# BedStrip.net
KiCad netlist of a schematic drawn in EAGLE
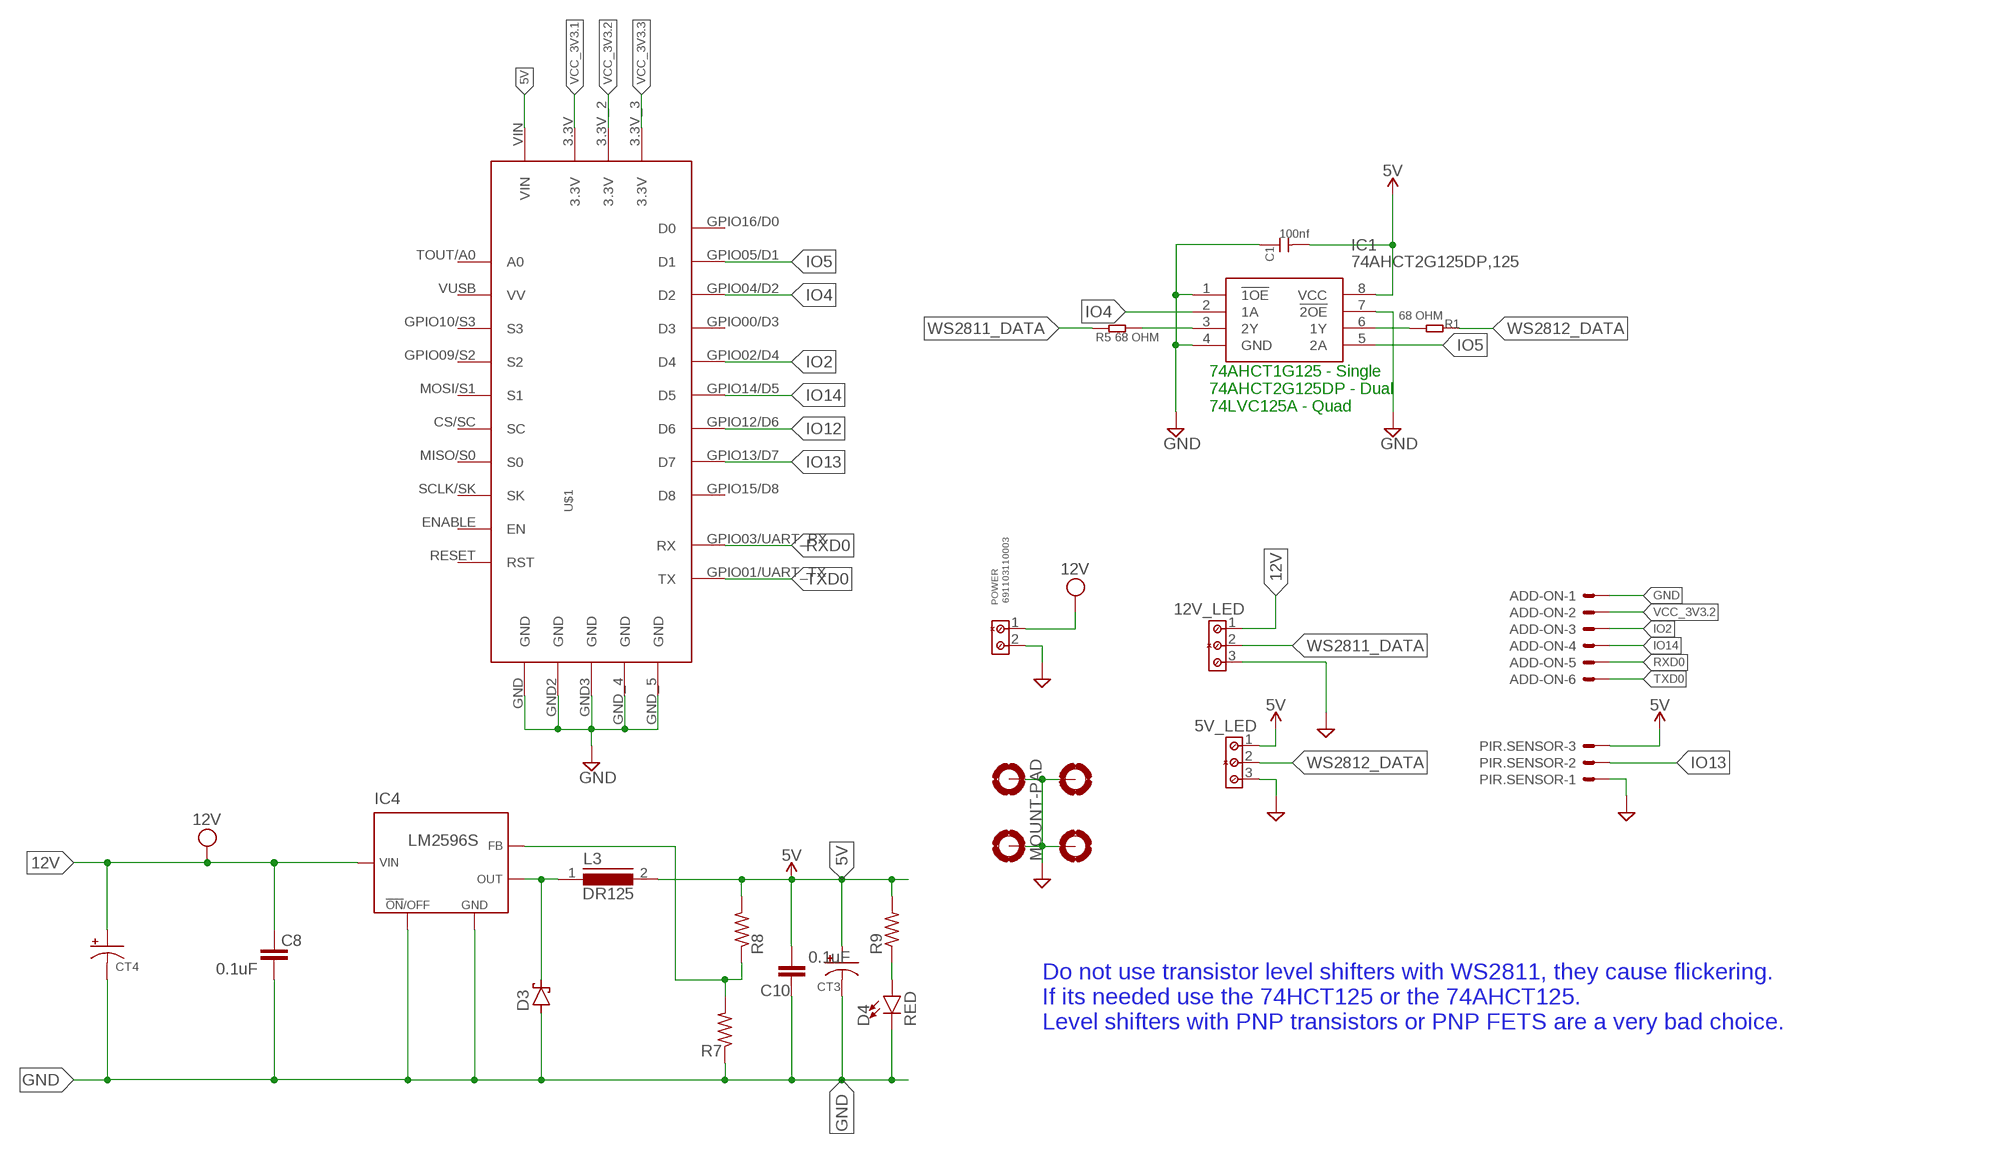
[diagram p0: schematic, sheet 1]

(export (version "E")
  (design (tool "Eeschema 10.0.6"))
  (components
    (comp (ref "5V_LED")
      (value "691103110003")
      (footprint "eagle-import:WR-TB_3.50-3.81_3POS")
      (libsource (lib "eagle-import") (part "CONN-WR-TBL-3POS"))
    )
    (comp (ref "12V_LED")
      (value "691103110003")
      (footprint "eagle-import:WR-TB_3.50-3.81_3POS")
      (libsource (lib "eagle-import") (part "CONN-WR-TBL-3POS"))
    )
    (comp (ref "ADD-ON")
      (value "JST-XH-06-PIN-VERT-ROUND-PAD")
      (footprint "eagle-import:JST-XH-06-VERT-ROUND-PAD")
      (libsource (lib "eagle-import") (part "JST-XH-06-PIN-VERT-ROUND-PAD"))
    )
    (comp (ref "C1")
      (value "100nf")
      (footprint "eagle-import:C0603")
      (fields (field (name "MPN") "CC0603KRX7R9BB104"))
      (libsource (lib "eagle-import") (part "CERAMIC-100NF-50V-10%-X7R(0603)"))
    )
    (comp (ref "C8")
      (value "0.1uF")
      (footprint "eagle-import:CAPC1608X85")
      (libsource (lib "eagle-import") (part "CCHIP-0603(1608-METRIC)_"))
    )
    (comp (ref "C10")
      (value "0.1uF")
      (footprint "eagle-import:CAPC1608X85")
      (libsource (lib "eagle-import") (part "CCHIP-0603(1608-METRIC)_"))
    )
    (comp (ref "CT3")
      (value "220UF")
      (footprint "eagle-import:CAPAE830X1050N")
      (libsource (lib "eagle-import") (part "C-POL-USECAP-8.5MM_"))
    )
    (comp (ref "CT4")
      (value "220UF")
      (footprint "eagle-import:CAPAE830X1050N")
      (libsource (lib "eagle-import") (part "C-POL-USECAP-8.5MM_"))
    )
    (comp (ref "D3")
      (value "SCHOTTKY-DIODESMD")
      (footprint "eagle-import:SMB")
      (libsource (lib "eagle-import") (part "SCHOTTKY-DIODESMD"))
    )
    (comp (ref "D4")
      (value "RED")
      (footprint "eagle-import:LED-0603")
      (libsource (lib "eagle-import") (part "LED-RED0603"))
    )
    (comp (ref "H1")
      (value "MOUNT-PAD-ROUND3.2")
      (footprint "eagle-import:3,2-PAD")
      (libsource (lib "eagle-import") (part "MOUNT-PAD-ROUND3.2"))
    )
    (comp (ref "H2")
      (value "MOUNT-PAD-ROUND3.2")
      (footprint "eagle-import:3,2-PAD")
      (libsource (lib "eagle-import") (part "MOUNT-PAD-ROUND3.2"))
    )
    (comp (ref "H3")
      (value "MOUNT-PAD")
      (footprint "eagle-import:3,2-PAD")
      (libsource (lib "eagle-import") (part "MOUNT-PAD-ROUND3.2"))
    )
    (comp (ref "H4")
      (value "MOUNT-PAD-ROUND3.2")
      (footprint "eagle-import:3,2-PAD")
      (libsource (lib "eagle-import") (part "MOUNT-PAD-ROUND3.2"))
    )
    (comp (ref "IC1")
      (value "74AHCT2G125DP,125")
      (footprint "eagle-import:SOP65P400X110-8N")
      (fields (field (name "MOUSER_PART_NUMBER") "771-AHCT2G125DP125"))
      (libsource (lib "eagle-import") (part "74AHCT2G125DP,125"))
    )
    (comp (ref "IC4")
      (value "LM2596S")
      (footprint "eagle-import:TO263-5")
      (fields (field (name "MF") "NATIONAL SEMICONDUCTOR") (field (name "MPN") "LM2596S-ADJ/NOPB"))
      (libsource (lib "eagle-import") (part "LM2596S"))
    )
    (comp (ref "L3")
      (value "DR125")
      (footprint "eagle-import:DR125")
      (libsource (lib "eagle-import") (part "DR125"))
    )
    (comp (ref "PIR.SENSOR")
      (value "JST-XH-03-PIN-VERT-ROUND-PAD")
      (footprint "eagle-import:JST-XH-03-VERT-ROUND-PAD")
      (libsource (lib "eagle-import") (part "JST-XH-03-PIN-VERT-ROUND-PAD"))
    )
    (comp (ref "POWER")
      (value "691103110003")
      (footprint "eagle-import:WR-TB_3.50-3.81_2POS")
      (libsource (lib "eagle-import") (part "CONN-WR-TBL-2POS"))
    )
    (comp (ref "R1")
      (value "68 OHM")
      (footprint "eagle-import:R0603")
      (fields (field (name "MPN") "RC0603FR-071K5L"))
      (libsource (lib "eagle-import") (part "SMD-RES-68R-1%-1/10W(0603)"))
    )
    (comp (ref "R5")
      (value "68 OHM")
      (footprint "eagle-import:R0603")
      (fields (field (name "MPN") "RC0603FR-071K5L"))
      (libsource (lib "eagle-import") (part "SMD-RES-68R-1%-1/10W(0603)"))
    )
    (comp (ref "R7")
      (value "R-US_R0603")
      (footprint "eagle-import:R0603")
      (libsource (lib "eagle-import") (part "R-US_R0603"))
    )
    (comp (ref "R8")
      (value "R-US_R0603")
      (footprint "eagle-import:R0603")
      (libsource (lib "eagle-import") (part "R-US_R0603"))
    )
    (comp (ref "R9")
      (value "R-US_R0603")
      (footprint "eagle-import:R0603")
      (libsource (lib "eagle-import") (part "R-US_R0603"))
    )
    (comp (ref "U$1")
      (value "DEVBOARD_ESP8266_NODEMCU_V3DEVBOARD")
      (footprint "eagle-import:DEVBOARD_ESP8266_NODEMCU_V3")
      (libsource (lib "eagle-import") (part "DEVBOARD_ESP8266_NODEMCU_V3DEVBOARD"))
    )
  )
  (nets
    (net (code "1") (name "5V") (class "Default")
      (node (ref "5V_LED") (pin "1") (pinfunction "1_1") (pintype "passive"))
      (node (ref "C1") (pin "2") (pinfunction "2_2") (pintype "passive"))
      (node (ref "C10") (pin "1") (pinfunction "1_1") (pintype "passive"))
      (node (ref "CT3") (pin "1") (pinfunction "+_1") (pintype "passive"))
      (node (ref "IC1") (pin "8") (pinfunction "VCC_8") (pintype "bidirectional"))
      (node (ref "L3") (pin "2") (pinfunction "2_2") (pintype "passive"))
      (node (ref "PIR.SENSOR") (pin "3") (pinfunction "S_3") (pintype "passive"))
      (node (ref "R8") (pin "2") (pinfunction "2_2") (pintype "passive"))
      (node (ref "R9") (pin "2") (pinfunction "2_2") (pintype "passive"))
      (node (ref "U$1") (pin "VIN") (pinfunction "VIN_VIN") (pintype "bidirectional"))
    )
    (net (code "2") (name "12V") (class "Default")
      (node (ref "12V_LED") (pin "1") (pinfunction "1_1") (pintype "passive"))
      (node (ref "C8") (pin "2") (pinfunction "2_2") (pintype "passive"))
      (node (ref "CT4") (pin "1") (pinfunction "+_1") (pintype "passive"))
      (node (ref "IC4") (pin "1") (pinfunction "VIN_1") (pintype "input"))
      (node (ref "POWER") (pin "1") (pinfunction "1_1") (pintype "passive"))
    )
    (net (code "3") (name "GND") (class "Default")
      (node (ref "12V_LED") (pin "3") (pinfunction "3_3") (pintype "passive"))
      (node (ref "5V_LED") (pin "3") (pinfunction "3_3") (pintype "passive"))
      (node (ref "ADD-ON") (pin "1") (pinfunction "S_1") (pintype "passive"))
      (node (ref "C1") (pin "1") (pinfunction "1_1") (pintype "passive"))
      (node (ref "C10") (pin "2") (pinfunction "2_2") (pintype "passive"))
      (node (ref "C8") (pin "1") (pinfunction "1_1") (pintype "passive"))
      (node (ref "CT3") (pin "2") (pinfunction "-_2") (pintype "passive"))
      (node (ref "CT4") (pin "2") (pinfunction "-_2") (pintype "passive"))
      (node (ref "D3") (pin "A") (pinfunction "A_A") (pintype "passive"))
      (node (ref "D4") (pin "C") (pinfunction "C_C") (pintype "passive"))
      (node (ref "H1") (pin "B3,2") (pinfunction "MOUNT_B3,2") (pintype "passive"))
      (node (ref "H2") (pin "B3,2") (pinfunction "MOUNT_B3,2") (pintype "passive"))
      (node (ref "H3") (pin "B3,2") (pinfunction "MOUNT_B3,2") (pintype "passive"))
      (node (ref "H4") (pin "B3,2") (pinfunction "MOUNT_B3,2") (pintype "passive"))
      (node (ref "IC1") (pin "1") (pinfunction "~{1OE}_1") (pintype "bidirectional"))
      (node (ref "IC1") (pin "4") (pinfunction "GND_4") (pintype "bidirectional"))
      (node (ref "IC1") (pin "7") (pinfunction "~{2OE}_7") (pintype "bidirectional"))
      (node (ref "IC4") (pin "3") (pinfunction "GND_3") (pintype "power_in"))
      (node (ref "IC4") (pin "5") (pinfunction "~{ON}/OFF_5") (pintype "input"))
      (node (ref "IC4") (pin "6") (pinfunction "GND_6") (pintype "power_in"))
      (node (ref "PIR.SENSOR") (pin "1") (pinfunction "S_1") (pintype "passive"))
      (node (ref "POWER") (pin "2") (pinfunction "2_2") (pintype "passive"))
      (node (ref "R7") (pin "1") (pinfunction "1_1") (pintype "passive"))
      (node (ref "U$1") (pin "GND") (pinfunction "GND_GND") (pintype "bidirectional"))
      (node (ref "U$1") (pin "GND2") (pinfunction "GND_GND2") (pintype "bidirectional"))
      (node (ref "U$1") (pin "GND3") (pinfunction "GND_GND3") (pintype "bidirectional"))
      (node (ref "U$1") (pin "GND_4") (pinfunction "GND_GND_4") (pintype "bidirectional"))
      (node (ref "U$1") (pin "GND_5") (pinfunction "GND_GND_5") (pintype "bidirectional"))
    )
    (net (code "4") (name "IO2") (class "Default")
      (node (ref "ADD-ON") (pin "3") (pinfunction "S_3") (pintype "passive"))
      (node (ref "U$1") (pin "GPIO02/D4") (pinfunction "D4_GPIO02/D4") (pintype "bidirectional"))
    )
    (net (code "5") (name "IO4") (class "Default")
      (node (ref "IC1") (pin "2") (pinfunction "1A_2") (pintype "bidirectional"))
      (node (ref "U$1") (pin "GPIO04/D2") (pinfunction "D2_GPIO04/D2") (pintype "bidirectional"))
    )
    (net (code "6") (name "IO5") (class "Default")
      (node (ref "IC1") (pin "5") (pinfunction "2A_5") (pintype "bidirectional"))
      (node (ref "U$1") (pin "GPIO05/D1") (pinfunction "D1_GPIO05/D1") (pintype "bidirectional"))
    )
    (net (code "7") (name "IO12") (class "Default")
      (node (ref "U$1") (pin "GPIO12/D6") (pinfunction "D6_GPIO12/D6") (pintype "bidirectional"))
    )
    (net (code "8") (name "IO13") (class "Default")
      (node (ref "PIR.SENSOR") (pin "2") (pinfunction "S_2") (pintype "passive"))
      (node (ref "U$1") (pin "GPIO13/D7") (pinfunction "D7_GPIO13/D7") (pintype "bidirectional"))
    )
    (net (code "9") (name "IO14") (class "Default")
      (node (ref "ADD-ON") (pin "4") (pinfunction "S_4") (pintype "passive"))
      (node (ref "U$1") (pin "GPIO14/D5") (pinfunction "D5_GPIO14/D5") (pintype "bidirectional"))
    )
    (net (code "10") (name "Net-(D4-PadA)") (class "Default")
      (node (ref "D4") (pin "A") (pinfunction "A_A") (pintype "passive"))
      (node (ref "R9") (pin "1") (pinfunction "1_1") (pintype "passive"))
    )
    (net (code "11") (name "Net-(IC1-1Y)") (class "Default")
      (node (ref "IC1") (pin "6") (pinfunction "1Y_6") (pintype "bidirectional"))
      (node (ref "R1") (pin "2") (pinfunction "2_2") (pintype "passive"))
    )
    (net (code "12") (name "Net-(IC1-2Y)") (class "Default")
      (node (ref "IC1") (pin "3") (pinfunction "2Y_3") (pintype "bidirectional"))
      (node (ref "R5") (pin "2") (pinfunction "2_2") (pintype "passive"))
    )
    (net (code "13") (name "Net-(IC4-FB)") (class "Default")
      (node (ref "IC4") (pin "4") (pinfunction "FB_4") (pintype "input"))
      (node (ref "R7") (pin "2") (pinfunction "2_2") (pintype "passive"))
      (node (ref "R8") (pin "1") (pinfunction "1_1") (pintype "passive"))
    )
    (net (code "14") (name "Net-(IC4-OUT)") (class "Default")
      (node (ref "D3") (pin "C") (pinfunction "C_C") (pintype "passive"))
      (node (ref "IC4") (pin "2") (pinfunction "OUT_2") (pintype "output"))
      (node (ref "L3") (pin "1") (pinfunction "1_1") (pintype "passive"))
    )
    (net (code "15") (name "RXD0") (class "Default")
      (node (ref "ADD-ON") (pin "5") (pinfunction "S_5") (pintype "passive"))
      (node (ref "U$1") (pin "GPIO03/UART_RX") (pinfunction "RX_GPIO03/UART_RX") (pintype "bidirectional"))
    )
    (net (code "16") (name "TXD0") (class "Default")
      (node (ref "ADD-ON") (pin "6") (pinfunction "S_6") (pintype "passive"))
      (node (ref "U$1") (pin "GPIO01/UART_TX") (pinfunction "TX_GPIO01/UART_TX") (pintype "bidirectional"))
    )
    (net (code "17") (name "VCC_3V3.1") (class "Default")
      (node (ref "U$1") (pin "3.3V") (pinfunction "3.3V_3.3V") (pintype "bidirectional"))
    )
    (net (code "18") (name "VCC_3V3.2") (class "Default")
      (node (ref "ADD-ON") (pin "2") (pinfunction "S_2") (pintype "passive"))
      (node (ref "U$1") (pin "3.3V_2") (pinfunction "3.3V_3.3V_2") (pintype "bidirectional"))
    )
    (net (code "19") (name "VCC_3V3.3") (class "Default")
      (node (ref "U$1") (pin "3.3V_3") (pinfunction "3.3V_3.3V_3") (pintype "bidirectional"))
    )
    (net (code "20") (name "WS2811_DATA") (class "Default")
      (node (ref "12V_LED") (pin "2") (pinfunction "2_2") (pintype "passive"))
      (node (ref "R5") (pin "1") (pinfunction "1_1") (pintype "passive"))
    )
    (net (code "21") (name "WS2812_DATA") (class "Default")
      (node (ref "5V_LED") (pin "2") (pinfunction "2_2") (pintype "passive"))
      (node (ref "R1") (pin "1") (pinfunction "1_1") (pintype "passive"))
    )
    (net (code "22") (name "unconnected-(U$1-A0-PadTOUT{slash}A0)") (class "Default")
      (node (ref "U$1") (pin "TOUT/A0") (pinfunction "A0_TOUT/A0") (pintype "bidirectional"))
    )
    (net (code "23") (name "unconnected-(U$1-D0-PadGPIO16{slash}D0)") (class "Default")
      (node (ref "U$1") (pin "GPIO16/D0") (pinfunction "D0_GPIO16/D0") (pintype "bidirectional"))
    )
    (net (code "24") (name "unconnected-(U$1-D3-PadGPIO00{slash}D3)") (class "Default")
      (node (ref "U$1") (pin "GPIO00/D3") (pinfunction "D3_GPIO00/D3") (pintype "bidirectional"))
    )
    (net (code "25") (name "unconnected-(U$1-D8-PadGPIO15{slash}D8)") (class "Default")
      (node (ref "U$1") (pin "GPIO15/D8") (pinfunction "D8_GPIO15/D8") (pintype "bidirectional"))
    )
    (net (code "26") (name "unconnected-(U$1-EN-PadENABLE)") (class "Default")
      (node (ref "U$1") (pin "ENABLE") (pinfunction "EN_ENABLE") (pintype "bidirectional"))
    )
    (net (code "27") (name "unconnected-(U$1-RST-PadRESET)") (class "Default")
      (node (ref "U$1") (pin "RESET") (pinfunction "RST_RESET") (pintype "bidirectional"))
    )
    (net (code "28") (name "unconnected-(U$1-S0-PadMISO{slash}S0)") (class "Default")
      (node (ref "U$1") (pin "MISO/S0") (pinfunction "S0_MISO/S0") (pintype "bidirectional"))
    )
    (net (code "29") (name "unconnected-(U$1-S1-PadMOSI{slash}S1)") (class "Default")
      (node (ref "U$1") (pin "MOSI/S1") (pinfunction "S1_MOSI/S1") (pintype "bidirectional"))
    )
    (net (code "30") (name "unconnected-(U$1-S2-PadGPIO09{slash}S2)") (class "Default")
      (node (ref "U$1") (pin "GPIO09/S2") (pinfunction "S2_GPIO09/S2") (pintype "bidirectional"))
    )
    (net (code "31") (name "unconnected-(U$1-S3-PadGPIO10{slash}S3)") (class "Default")
      (node (ref "U$1") (pin "GPIO10/S3") (pinfunction "S3_GPIO10/S3") (pintype "bidirectional"))
    )
    (net (code "32") (name "unconnected-(U$1-SC-PadCS{slash}SC)") (class "Default")
      (node (ref "U$1") (pin "CS/SC") (pinfunction "SC_CS/SC") (pintype "bidirectional"))
    )
    (net (code "33") (name "unconnected-(U$1-SK-PadSCLK{slash}SK)") (class "Default")
      (node (ref "U$1") (pin "SCLK/SK") (pinfunction "SK_SCLK/SK") (pintype "bidirectional"))
    )
    (net (code "34") (name "unconnected-(U$1-VV-PadVUSB)") (class "Default")
      (node (ref "U$1") (pin "VUSB") (pinfunction "VV_VUSB") (pintype "bidirectional"))
    )
  )
)
